# QCopterMV_SD_Sch.net
KiCad netlist of a schematic drawn in Altium Designer
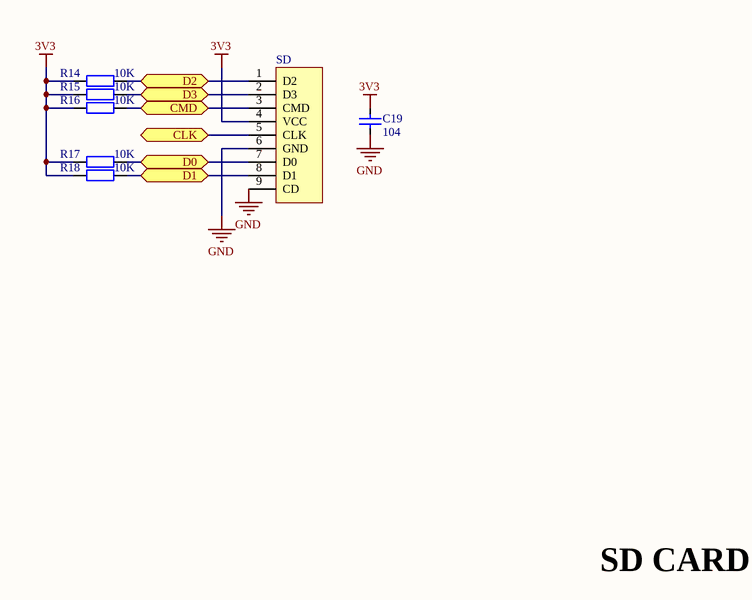
[diagram p0: QCopterMV_SD_Sch.SchDoc]

(export (version "E")
  (design (tool "Eeschema 10.0.6"))
  (components
    (comp (ref "C19")
      (value "104")
      (footprint "PCB_Passive:CAP_0603")
      (description "Capacitor")
      (fields (field (name "Comment") "Cap_0603"))
      (libsource (lib "SCH_Passive") (part "Cap_0603"))
    )
    (comp (ref "R14")
      (value "10K")
      (footprint "PCB_Passive:RES_0603")
      (description "Resistor")
      (fields (field (name "Comment") "Res_0603"))
      (libsource (lib "SCH_Passive") (part "Res_0603"))
    )
    (comp (ref "R15")
      (value "10K")
      (footprint "PCB_Passive:RES_0603")
      (description "Resistor")
      (fields (field (name "Comment") "Res_0603"))
      (libsource (lib "SCH_Passive") (part "Res_0603"))
    )
    (comp (ref "R16")
      (value "10K")
      (footprint "PCB_Passive:RES_0603")
      (description "Resistor")
      (fields (field (name "Comment") "Res_0603"))
      (libsource (lib "SCH_Passive") (part "Res_0603"))
    )
    (comp (ref "R17")
      (value "10K")
      (footprint "PCB_Passive:RES_0603")
      (description "Resistor")
      (fields (field (name "Comment") "Res_0603"))
      (libsource (lib "SCH_Passive") (part "Res_0603"))
    )
    (comp (ref "R18")
      (value "10K")
      (footprint "PCB_Passive:RES_0603")
      (description "Resistor")
      (fields (field (name "Comment") "Res_0603"))
      (libsource (lib "SCH_Passive") (part "Res_0603"))
    )
    (comp (ref "SD")
      (value "SD_Card_TF")
      (footprint "PCB_SDCard:SD_Card_TF")
      (description "SD")
      (libsource (lib "SCH_SDCard") (part "SD_Card_TF"))
    )
  )
  (nets
    (net (code "1") (name "/CLK") (class "Default")
      (node (ref "SD") (pin "5") (pinfunction "CLK_5") (pintype "passive"))
    )
    (net (code "2") (name "/CMD") (class "Default")
      (node (ref "R16") (pin "2") (pinfunction "2_2") (pintype "passive"))
      (node (ref "SD") (pin "3") (pinfunction "CMD_3") (pintype "passive"))
    )
    (net (code "3") (name "/D0") (class "Default")
      (node (ref "R17") (pin "2") (pinfunction "2_2") (pintype "passive"))
      (node (ref "SD") (pin "7") (pinfunction "D0_7") (pintype "passive"))
    )
    (net (code "4") (name "/D1") (class "Default")
      (node (ref "R18") (pin "2") (pinfunction "2_2") (pintype "passive"))
      (node (ref "SD") (pin "8") (pinfunction "D1_8") (pintype "passive"))
    )
    (net (code "5") (name "/D2") (class "Default")
      (node (ref "R14") (pin "2") (pinfunction "2_2") (pintype "passive"))
      (node (ref "SD") (pin "1") (pinfunction "D2_1") (pintype "passive"))
    )
    (net (code "6") (name "/D3") (class "Default")
      (node (ref "R15") (pin "2") (pinfunction "2_2") (pintype "passive"))
      (node (ref "SD") (pin "2") (pinfunction "D3_2") (pintype "passive"))
    )
    (net (code "8") (name "3V3") (class "Default")
      (node (ref "C19") (pin "2") (pinfunction "2_2") (pintype "passive"))
      (node (ref "R14") (pin "1") (pinfunction "1_1") (pintype "passive"))
      (node (ref "R15") (pin "1") (pinfunction "1_1") (pintype "passive"))
      (node (ref "R16") (pin "1") (pinfunction "1_1") (pintype "passive"))
      (node (ref "R17") (pin "1") (pinfunction "1_1") (pintype "passive"))
      (node (ref "R18") (pin "1") (pinfunction "1_1") (pintype "passive"))
      (node (ref "SD") (pin "4") (pinfunction "VCC_4") (pintype "passive"))
    )
    (net (code "9") (name "GND") (class "Default")
      (node (ref "C19") (pin "1") (pinfunction "1_1") (pintype "passive"))
      (node (ref "SD") (pin "6") (pinfunction "GND_6") (pintype "passive"))
      (node (ref "SD") (pin "9") (pinfunction "CD_9") (pintype "passive"))
    )
  )
)
